# inst_amp.net
KiCad netlist of a schematic drawn in EAGLE
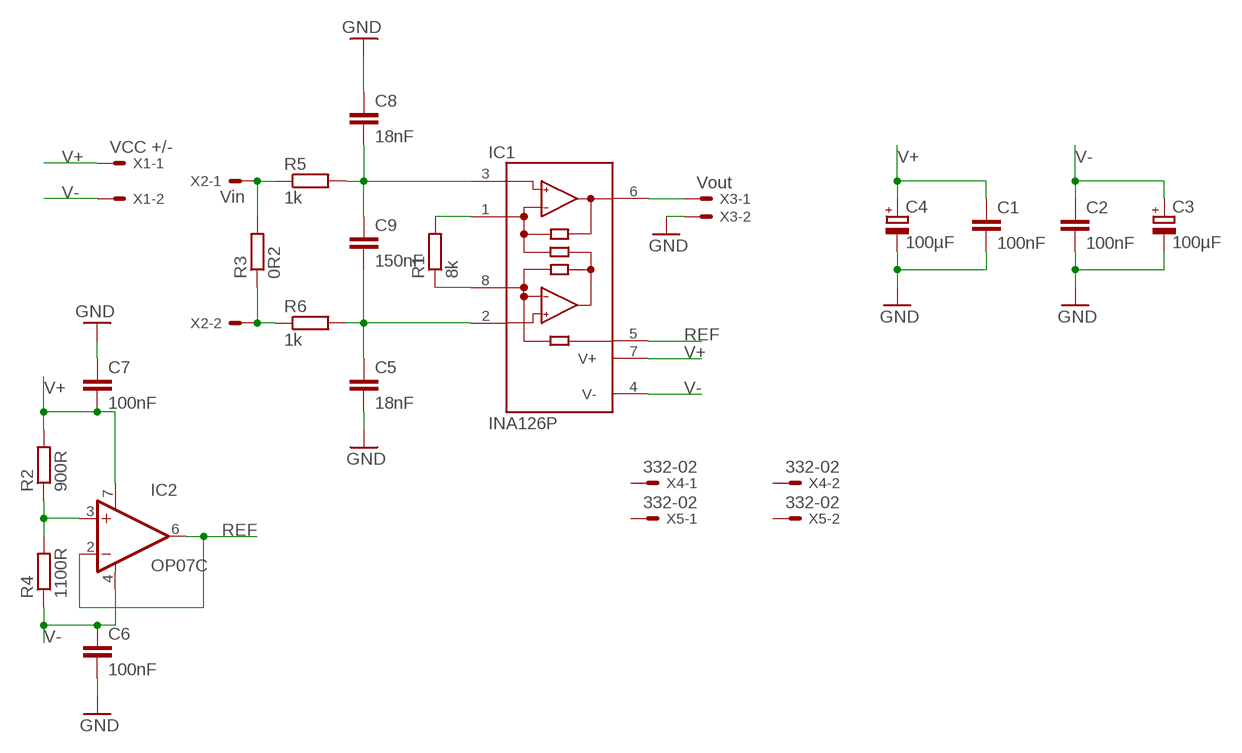
[diagram p0: schematic, sheet 1]

(export (version "E")
  (design (tool "Eeschema 10.0.6"))
  (components
    (comp (ref "C1")
      (value "100nF")
      (footprint "eagle-import:C050-025X075")
      (libsource (lib "eagle-import") (part "C-EU050-025X075"))
    )
    (comp (ref "C2")
      (value "100nF")
      (footprint "eagle-import:C050-025X075")
      (libsource (lib "eagle-import") (part "C-EU050-025X075"))
    )
    (comp (ref "C3")
      (value "100µF")
      (footprint "eagle-import:E5-10,5")
      (libsource (lib "eagle-import") (part "CPOL-EUE5-10.5"))
    )
    (comp (ref "C4")
      (value "100µF")
      (footprint "eagle-import:E5-10,5")
      (libsource (lib "eagle-import") (part "CPOL-EUE5-10.5"))
    )
    (comp (ref "C5")
      (value "18nF")
      (footprint "eagle-import:C050-024X044")
      (libsource (lib "eagle-import") (part "C-EU050-024X044"))
    )
    (comp (ref "C6")
      (value "100nF")
      (footprint "eagle-import:C050-025X075")
      (libsource (lib "eagle-import") (part "C-EU050-025X075"))
    )
    (comp (ref "C7")
      (value "100nF")
      (footprint "eagle-import:C050-025X075")
      (libsource (lib "eagle-import") (part "C-EU050-025X075"))
    )
    (comp (ref "C8")
      (value "18nF")
      (footprint "eagle-import:C050-024X044")
      (libsource (lib "eagle-import") (part "C-EU050-024X044"))
    )
    (comp (ref "C9")
      (value "150nF")
      (footprint "eagle-import:C050-025X075")
      (libsource (lib "eagle-import") (part "C-EU050-025X075"))
    )
    (comp (ref "IC1")
      (value "INA126P")
      (footprint "eagle-import:DIL08")
      (fields (field (name "MF") "TEXAS INSTRUMENT CONNECTORS"))
      (libsource (lib "eagle-import") (part "INA126P"))
    )
    (comp (ref "IC2")
      (value "OP07C")
      (footprint "eagle-import:DIL08")
      (fields (field (name "MPN") "AD8001ANZ"))
      (libsource (lib "eagle-import") (part "OPA658P"))
    )
    (comp (ref "R1")
      (value "8k")
      (footprint "eagle-import:0207_10")
      (libsource (lib "eagle-import") (part "R-EU_0207/10"))
    )
    (comp (ref "R2")
      (value "900R")
      (footprint "eagle-import:0207_10")
      (libsource (lib "eagle-import") (part "R-EU_0207/10"))
    )
    (comp (ref "R3")
      (value "0R2")
      (footprint "eagle-import:0414_15")
      (libsource (lib "eagle-import") (part "R-EU_0414/15"))
    )
    (comp (ref "R4")
      (value "1100R")
      (footprint "eagle-import:0207_10")
      (libsource (lib "eagle-import") (part "R-EU_0207/10"))
    )
    (comp (ref "R5")
      (value "1k")
      (footprint "eagle-import:0207_10")
      (libsource (lib "eagle-import") (part "resistor_R-EU_0207/10"))
    )
    (comp (ref "R6")
      (value "1k")
      (footprint "eagle-import:0207_10")
      (libsource (lib "eagle-import") (part "resistor_R-EU_0207/10"))
    )
    (comp (ref "X1")
      (value "VCC +/-")
      (footprint "eagle-import:22-23-2021")
      (fields (field (name "MF") "MOLEX") (field (name "MPN") "22-23-2021"))
      (libsource (lib "eagle-import") (part "22-23-2021"))
    )
    (comp (ref "X2")
      (value "Vin")
      (footprint "eagle-import:22-23-2021")
      (fields (field (name "MF") "MOLEX") (field (name "MPN") "22-23-2021"))
      (libsource (lib "eagle-import") (part "22-23-2021"))
    )
    (comp (ref "X3")
      (value "Vout")
      (footprint "eagle-import:22-23-2021")
      (fields (field (name "MF") "MOLEX") (field (name "MPN") "22-23-2021"))
      (libsource (lib "eagle-import") (part "22-23-2021"))
    )
    (comp (ref "X4")
      (value "332-02")
      (footprint "eagle-import:332-02")
      (libsource (lib "eagle-import") (part "332-02"))
    )
    (comp (ref "X5")
      (value "332-02")
      (footprint "eagle-import:332-02")
      (libsource (lib "eagle-import") (part "332-02"))
    )
  )
  (nets
    (net (code "1") (name "/REF") (class "Default")
      (node (ref "IC1") (pin "5") (pinfunction "REF_5") (pintype "passive"))
      (node (ref "IC2") (pin "2") (pinfunction "-IN_2") (pintype "input"))
      (node (ref "IC2") (pin "6") (pinfunction "OUT_6") (pintype "output"))
    )
    (net (code "2") (name "/V+") (class "Default")
      (node (ref "C1") (pin "1") (pinfunction "1_1") (pintype "passive"))
      (node (ref "C4") (pin "+") (pinfunction "+_+") (pintype "passive"))
      (node (ref "C7") (pin "2") (pinfunction "2_2") (pintype "passive"))
      (node (ref "IC1") (pin "7") (pinfunction "V+_7") (pintype "power_in"))
      (node (ref "IC2") (pin "7") (pinfunction "V+_7") (pintype "power_in"))
      (node (ref "R2") (pin "2") (pinfunction "2_2") (pintype "passive"))
      (node (ref "X1") (pin "1") (pinfunction "S_1") (pintype "passive"))
    )
    (net (code "3") (name "/V-") (class "Default")
      (node (ref "C2") (pin "1") (pinfunction "1_1") (pintype "passive"))
      (node (ref "C3") (pin "+") (pinfunction "+_+") (pintype "passive"))
      (node (ref "C6") (pin "1") (pinfunction "1_1") (pintype "passive"))
      (node (ref "IC1") (pin "4") (pinfunction "V-_4") (pintype "power_in"))
      (node (ref "IC2") (pin "4") (pinfunction "V-_4") (pintype "power_in"))
      (node (ref "R4") (pin "1") (pinfunction "1_1") (pintype "passive"))
      (node (ref "X1") (pin "2") (pinfunction "S_2") (pintype "passive"))
    )
    (net (code "4") (name "GND") (class "Default")
      (node (ref "C1") (pin "2") (pinfunction "2_2") (pintype "passive"))
      (node (ref "C2") (pin "2") (pinfunction "2_2") (pintype "passive"))
      (node (ref "C3") (pin "-") (pinfunction "-_-") (pintype "passive"))
      (node (ref "C4") (pin "-") (pinfunction "-_-") (pintype "passive"))
      (node (ref "C5") (pin "2") (pinfunction "2_2") (pintype "passive"))
      (node (ref "C6") (pin "2") (pinfunction "2_2") (pintype "passive"))
      (node (ref "C7") (pin "1") (pinfunction "1_1") (pintype "passive"))
      (node (ref "C8") (pin "1") (pinfunction "1_1") (pintype "passive"))
      (node (ref "X3") (pin "2") (pinfunction "S_2") (pintype "passive"))
    )
    (net (code "5") (name "Net-(IC1-+IN)") (class "Default")
      (node (ref "C8") (pin "2") (pinfunction "2_2") (pintype "passive"))
      (node (ref "C9") (pin "1") (pinfunction "1_1") (pintype "passive"))
      (node (ref "IC1") (pin "3") (pinfunction "+IN_3") (pintype "input"))
      (node (ref "R5") (pin "2") (pinfunction "2_2") (pintype "passive"))
    )
    (net (code "6") (name "Net-(IC1--IN)") (class "Default")
      (node (ref "C5") (pin "1") (pinfunction "1_1") (pintype "passive"))
      (node (ref "C9") (pin "2") (pinfunction "2_2") (pintype "passive"))
      (node (ref "IC1") (pin "2") (pinfunction "-IN_2") (pintype "input"))
      (node (ref "R6") (pin "2") (pinfunction "2_2") (pintype "passive"))
    )
    (net (code "7") (name "Net-(IC1-OUT)") (class "Default")
      (node (ref "IC1") (pin "6") (pinfunction "OUT_6") (pintype "output"))
      (node (ref "X3") (pin "1") (pinfunction "S_1") (pintype "passive"))
    )
    (net (code "8") (name "Net-(IC1-RG-Pad1)") (class "Default")
      (node (ref "IC1") (pin "1") (pinfunction "RG_1") (pintype "passive"))
      (node (ref "R1") (pin "2") (pinfunction "2_2") (pintype "passive"))
    )
    (net (code "9") (name "Net-(IC1-RG-Pad8)") (class "Default")
      (node (ref "IC1") (pin "8") (pinfunction "RG_8") (pintype "passive"))
      (node (ref "R1") (pin "1") (pinfunction "1_1") (pintype "passive"))
    )
    (net (code "10") (name "Net-(IC2-+IN)") (class "Default")
      (node (ref "IC2") (pin "3") (pinfunction "+IN_3") (pintype "input"))
      (node (ref "R2") (pin "1") (pinfunction "1_1") (pintype "passive"))
      (node (ref "R4") (pin "2") (pinfunction "2_2") (pintype "passive"))
    )
    (net (code "11") (name "Net-(X2A-S)") (class "Default")
      (node (ref "R3") (pin "2") (pinfunction "2_2") (pintype "passive"))
      (node (ref "R5") (pin "1") (pinfunction "1_1") (pintype "passive"))
      (node (ref "X2") (pin "1") (pinfunction "S_1") (pintype "passive"))
    )
    (net (code "12") (name "Net-(X2B-S)") (class "Default")
      (node (ref "R3") (pin "1") (pinfunction "1_1") (pintype "passive"))
      (node (ref "R6") (pin "1") (pinfunction "1_1") (pintype "passive"))
      (node (ref "X2") (pin "2") (pinfunction "S_2") (pintype "passive"))
    )
    (net (code "13") (name "unconnected-(X4A-S-Pad1)") (class "Default")
      (node (ref "X4") (pin "1") (pinfunction "S_1") (pintype "passive"))
    )
    (net (code "14") (name "unconnected-(X4B-S-Pad2)") (class "Default")
      (node (ref "X4") (pin "2") (pinfunction "S_2") (pintype "passive"))
    )
    (net (code "15") (name "unconnected-(X5A-S-Pad1)") (class "Default")
      (node (ref "X5") (pin "1") (pinfunction "S_1") (pintype "passive"))
    )
    (net (code "16") (name "unconnected-(X5B-S-Pad2)") (class "Default")
      (node (ref "X5") (pin "2") (pinfunction "S_2") (pintype "passive"))
    )
  )
)
